# ESP32.net
KiCad netlist of a schematic drawn in Altium Designer
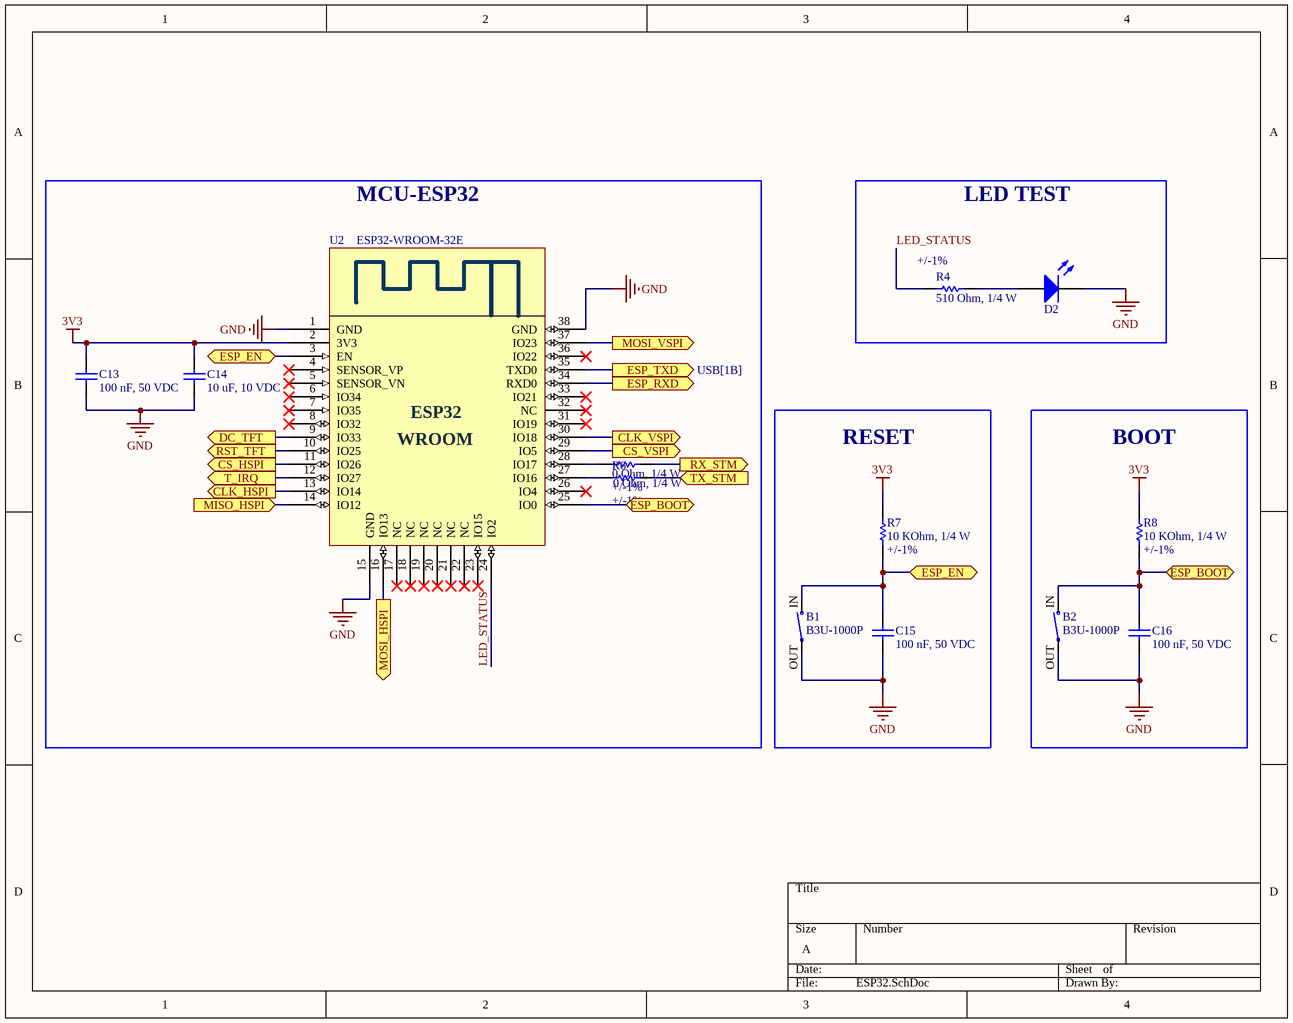
[diagram p0: ESP32.SchDoc]

(export (version "E")
  (design (tool "Eeschema 10.0.6"))
  (components
    (comp (ref "B1")
      (value "B3U-1000P")
      (footprint "SODFL4025X160N")
      (description "Switch Tactile N.O. SPST Round Button Gull Wing 0.05A 12VDC 1.5N SMD T/R")
      (fields (field (name "MF") "Omron") (field (name "MP") "B3U1000P"))
      (libsource (lib "B3U-1000P") (part "B3U-1000P"))
    )
    (comp (ref "B2")
      (value "B3U-1000P")
      (footprint "SODFL4025X160N")
      (description "Switch Tactile N.O. SPST Round Button Gull Wing 0.05A 12VDC 1.5N SMD T/R")
      (fields (field (name "MF") "Omron") (field (name "MP") "B3U1000P"))
      (libsource (lib "B3U-1000P") (part "B3U-1000P"))
    )
    (comp (ref "C13")
      (value "100 nF, 50 VDC")
      (footprint "CAP_0603")
      (description "CAP, size 0603, 100 nF, 50 VDC")
      (fields (field (name "TOLERANCE") "+/-10%"))
      (libsource (lib "Altium_Ceramic_Cap") (part "0106031041050"))
    )
    (comp (ref "C14")
      (value "10 uF, 10 VDC")
      (footprint "CAP_0603")
      (description "CAP, size 0603, 10 uF, 10 VDC")
      (fields (field (name "TOLERANCE") "+/-10%"))
      (libsource (lib "Altium_Ceramic_Cap") (part "0106031061010"))
    )
    (comp (ref "C15")
      (value "100 nF, 50 VDC")
      (footprint "CAP_0603")
      (description "CAP, size 0603, 100 nF, 50 VDC")
      (fields (field (name "TOLERANCE") "+/-10%"))
      (libsource (lib "Altium_Ceramic_Cap") (part "0106031041050"))
    )
    (comp (ref "C16")
      (value "100 nF, 50 VDC")
      (footprint "CAP_0603")
      (description "CAP, size 0603, 100 nF, 50 VDC")
      (fields (field (name "TOLERANCE") "+/-10%"))
      (libsource (lib "Altium_Ceramic_Cap") (part "0106031041050"))
    )
    (comp (ref "D2")
      (value "LED SMD")
      (footprint "LED_0805_Blue")
      (description "LED")
      (libsource (lib "PIF_Library") (part "LED SMD"))
    )
    (comp (ref "R4")
      (value "510 Ohm, 1/4 W")
      (footprint "resistor_0603")
      (description "RES, size 0603, 510 Ohm, 1/4 W")
      (fields (field (name "RESISTANCE TOLERANCE") "+/-1%"))
      (libsource (lib "Altium_Resistor") (part "0006035111"))
    )
    (comp (ref "R5")
      (value "0 Ohm, 1/4 W")
      (footprint "resistor_0603")
      (description "RES, size 0603, 0 Ohm, 1/4 W")
      (fields (field (name "RESISTANCE TOLERANCE") "+/-1%"))
      (libsource (lib "Altium_Resistor") (part "0006030001"))
    )
    (comp (ref "R6")
      (value "0 Ohm, 1/4 W")
      (footprint "resistor_0603")
      (description "RES, size 0603, 0 Ohm, 1/4 W")
      (fields (field (name "RESISTANCE TOLERANCE") "+/-1%"))
      (libsource (lib "Altium_Resistor") (part "0006030001"))
    )
    (comp (ref "R7")
      (value "10 KOhm, 1/4 W")
      (footprint "resistor_0603")
      (description "RES, size 0603, 10 KOhm, 1/4 W")
      (fields (field (name "RESISTANCE TOLERANCE") "+/-1%"))
      (libsource (lib "Altium_Resistor") (part "0006031031"))
    )
    (comp (ref "R8")
      (value "10 KOhm, 1/4 W")
      (footprint "resistor_0603")
      (description "RES, size 0603, 10 KOhm, 1/4 W")
      (fields (field (name "RESISTANCE TOLERANCE") "+/-1%"))
      (libsource (lib "Altium_Resistor") (part "0006031031"))
    )
    (comp (ref "U2")
      (value "ESP32-WROOM-32E")
      (footprint "ESP32-WROOM")
      (fields (field (name "MFR") "Espressif Systems") (field (name "UTILIZED IC / PART") "ESP32-D0WD-V3"))
      (libsource (lib "YenDoo") (part "ESP32-WROOM"))
    )
  )
  (nets
    (net (code "1") (name "/CLK_HSPI") (class "Default")
      (node (ref "U2") (pin "13") (pinfunction "IO14_13") (pintype "bidirectional"))
    )
    (net (code "2") (name "/CLK_VSPI") (class "Default")
      (node (ref "U2") (pin "30") (pinfunction "IO18_30") (pintype "bidirectional"))
    )
    (net (code "3") (name "/CS_HSPI") (class "Default")
      (node (ref "U2") (pin "11") (pinfunction "IO26_11") (pintype "bidirectional"))
    )
    (net (code "4") (name "/CS_VSPI") (class "Default")
      (node (ref "U2") (pin "29") (pinfunction "IO5_29") (pintype "bidirectional"))
    )
    (net (code "5") (name "/DC_TFT") (class "Default")
      (node (ref "U2") (pin "9") (pinfunction "IO33_9") (pintype "bidirectional"))
    )
    (net (code "6") (name "/ESP_BOOT") (class "Default")
      (node (ref "B2") (pin "IN") (pinfunction "2_IN") (pintype "passive"))
      (node (ref "C16") (pin "2") (pinfunction "2_2") (pintype "passive"))
      (node (ref "R8") (pin "1") (pinfunction "1_1") (pintype "passive"))
      (node (ref "U2") (pin "25") (pinfunction "IO0_25") (pintype "bidirectional"))
    )
    (net (code "7") (name "/ESP_EN") (class "Default")
      (node (ref "B1") (pin "IN") (pinfunction "2_IN") (pintype "passive"))
      (node (ref "C15") (pin "2") (pinfunction "2_2") (pintype "passive"))
      (node (ref "R7") (pin "1") (pinfunction "1_1") (pintype "passive"))
      (node (ref "U2") (pin "3") (pinfunction "EN_3") (pintype "input"))
    )
    (net (code "8") (name "/ESP_RXD") (class "Default")
      (node (ref "U2") (pin "34") (pinfunction "RXD0_34") (pintype "bidirectional"))
    )
    (net (code "9") (name "/ESP_TXD") (class "Default")
      (node (ref "U2") (pin "35") (pinfunction "TXD0_35") (pintype "bidirectional"))
    )
    (net (code "10") (name "/LED_STATUS") (class "Default")
      (node (ref "R4") (pin "1") (pinfunction "1_1") (pintype "passive"))
      (node (ref "U2") (pin "24") (pinfunction "IO2_24") (pintype "bidirectional"))
    )
    (net (code "11") (name "/MISO_HSPI") (class "Default")
      (node (ref "U2") (pin "14") (pinfunction "IO12_14") (pintype "bidirectional"))
    )
    (net (code "12") (name "/MOSI_HSPI") (class "Default")
      (node (ref "U2") (pin "16") (pinfunction "IO13_16") (pintype "bidirectional"))
    )
    (net (code "13") (name "/MOSI_VSPI") (class "Default")
      (node (ref "U2") (pin "37") (pinfunction "IO23_37") (pintype "bidirectional"))
    )
    (net (code "14") (name "/RST_TFT") (class "Default")
      (node (ref "U2") (pin "10") (pinfunction "IO25_10") (pintype "bidirectional"))
    )
    (net (code "15") (name "/RX_STM") (class "Default")
      (node (ref "R5") (pin "1") (pinfunction "1_1") (pintype "passive"))
    )
    (net (code "16") (name "/TX_STM") (class "Default")
      (node (ref "R6") (pin "1") (pinfunction "1_1") (pintype "passive"))
    )
    (net (code "17") (name "/T_IRQ") (class "Default")
      (node (ref "U2") (pin "12") (pinfunction "IO27_12") (pintype "bidirectional"))
    )
    (net (code "18") (name "3V3") (class "Default")
      (node (ref "C13") (pin "2") (pinfunction "2_2") (pintype "passive"))
      (node (ref "C14") (pin "2") (pinfunction "2_2") (pintype "passive"))
      (node (ref "R7") (pin "2") (pinfunction "2_2") (pintype "passive"))
      (node (ref "R8") (pin "2") (pinfunction "2_2") (pintype "passive"))
      (node (ref "U2") (pin "2") (pinfunction "3V3_2") (pintype "power_in"))
    )
    (net (code "19") (name "GND") (class "Default")
      (node (ref "B1") (pin "OUT") (pinfunction "1_OUT") (pintype "passive"))
      (node (ref "B2") (pin "OUT") (pinfunction "1_OUT") (pintype "passive"))
      (node (ref "C13") (pin "1") (pinfunction "1_1") (pintype "passive"))
      (node (ref "C14") (pin "1") (pinfunction "1_1") (pintype "passive"))
      (node (ref "C15") (pin "1") (pinfunction "1_1") (pintype "passive"))
      (node (ref "C16") (pin "1") (pinfunction "1_1") (pintype "passive"))
      (node (ref "D2") (pin "2") (pinfunction "K_2") (pintype "passive"))
      (node (ref "U2") (pin "1") (pinfunction "GND_1") (pintype "power_in"))
      (node (ref "U2") (pin "15") (pinfunction "GND_15") (pintype "power_in"))
      (node (ref "U2") (pin "38") (pinfunction "GND_38") (pintype "bidirectional"))
    )
    (net (code "20") (name "Net-(D2-A)") (class "Default")
      (node (ref "D2") (pin "1") (pinfunction "A_1") (pintype "passive"))
      (node (ref "R4") (pin "2") (pinfunction "2_2") (pintype "passive"))
    )
    (net (code "21") (name "Net-(U2-IO16)") (class "Default")
      (node (ref "R6") (pin "2") (pinfunction "2_2") (pintype "passive"))
      (node (ref "U2") (pin "27") (pinfunction "IO16_27") (pintype "bidirectional"))
    )
    (net (code "22") (name "Net-(U2-IO17)") (class "Default")
      (node (ref "R5") (pin "2") (pinfunction "2_2") (pintype "passive"))
      (node (ref "U2") (pin "28") (pinfunction "IO17_28") (pintype "bidirectional"))
    )
    (net (code "23") (name "unconnected-(U2-IO4-Pad26)") (class "Default")
      (node (ref "U2") (pin "26") (pinfunction "IO4_26") (pintype "bidirectional+no_connect"))
    )
    (net (code "24") (name "unconnected-(U2-IO15-Pad23)") (class "Default")
      (node (ref "U2") (pin "23") (pinfunction "IO15_23") (pintype "bidirectional+no_connect"))
    )
    (net (code "25") (name "unconnected-(U2-IO19-Pad31)") (class "Default")
      (node (ref "U2") (pin "31") (pinfunction "IO19_31") (pintype "bidirectional+no_connect"))
    )
    (net (code "26") (name "unconnected-(U2-IO21-Pad33)") (class "Default")
      (node (ref "U2") (pin "33") (pinfunction "IO21_33") (pintype "bidirectional+no_connect"))
    )
    (net (code "27") (name "unconnected-(U2-IO22-Pad36)") (class "Default")
      (node (ref "U2") (pin "36") (pinfunction "IO22_36") (pintype "bidirectional+no_connect"))
    )
    (net (code "28") (name "unconnected-(U2-IO32-Pad8)") (class "Default")
      (node (ref "U2") (pin "8") (pinfunction "IO32_8") (pintype "bidirectional+no_connect"))
    )
    (net (code "29") (name "unconnected-(U2-IO34-Pad6)") (class "Default")
      (node (ref "U2") (pin "6") (pinfunction "IO34_6") (pintype "input+no_connect"))
    )
    (net (code "30") (name "unconnected-(U2-IO35-Pad7)") (class "Default")
      (node (ref "U2") (pin "7") (pinfunction "IO35_7") (pintype "input+no_connect"))
    )
    (net (code "31") (name "unconnected-(U2-NC-Pad17)") (class "Default")
      (node (ref "U2") (pin "17") (pinfunction "NC_17") (pintype "tri_state+no_connect"))
    )
    (net (code "32") (name "unconnected-(U2-NC-Pad18)") (class "Default")
      (node (ref "U2") (pin "18") (pinfunction "NC_18") (pintype "tri_state+no_connect"))
    )
    (net (code "33") (name "unconnected-(U2-NC-Pad19)") (class "Default")
      (node (ref "U2") (pin "19") (pinfunction "NC_19") (pintype "tri_state+no_connect"))
    )
    (net (code "34") (name "unconnected-(U2-NC-Pad20)") (class "Default")
      (node (ref "U2") (pin "20") (pinfunction "NC_20") (pintype "tri_state+no_connect"))
    )
    (net (code "35") (name "unconnected-(U2-NC-Pad21)") (class "Default")
      (node (ref "U2") (pin "21") (pinfunction "NC_21") (pintype "tri_state+no_connect"))
    )
    (net (code "36") (name "unconnected-(U2-NC-Pad22)") (class "Default")
      (node (ref "U2") (pin "22") (pinfunction "NC_22") (pintype "tri_state+no_connect"))
    )
    (net (code "37") (name "unconnected-(U2-NC-Pad32)") (class "Default")
      (node (ref "U2") (pin "32") (pinfunction "NC_32") (pintype "tri_state+no_connect"))
    )
    (net (code "38") (name "unconnected-(U2-SENSOR_VN-Pad5)") (class "Default")
      (node (ref "U2") (pin "5") (pinfunction "SENSOR_VN_5") (pintype "input+no_connect"))
    )
    (net (code "39") (name "unconnected-(U2-SENSOR_VP-Pad4)") (class "Default")
      (node (ref "U2") (pin "4") (pinfunction "SENSOR_VP_4") (pintype "input+no_connect"))
    )
  )
)
